# full_adder.net
KiCad netlist of a schematic drawn in EAGLE
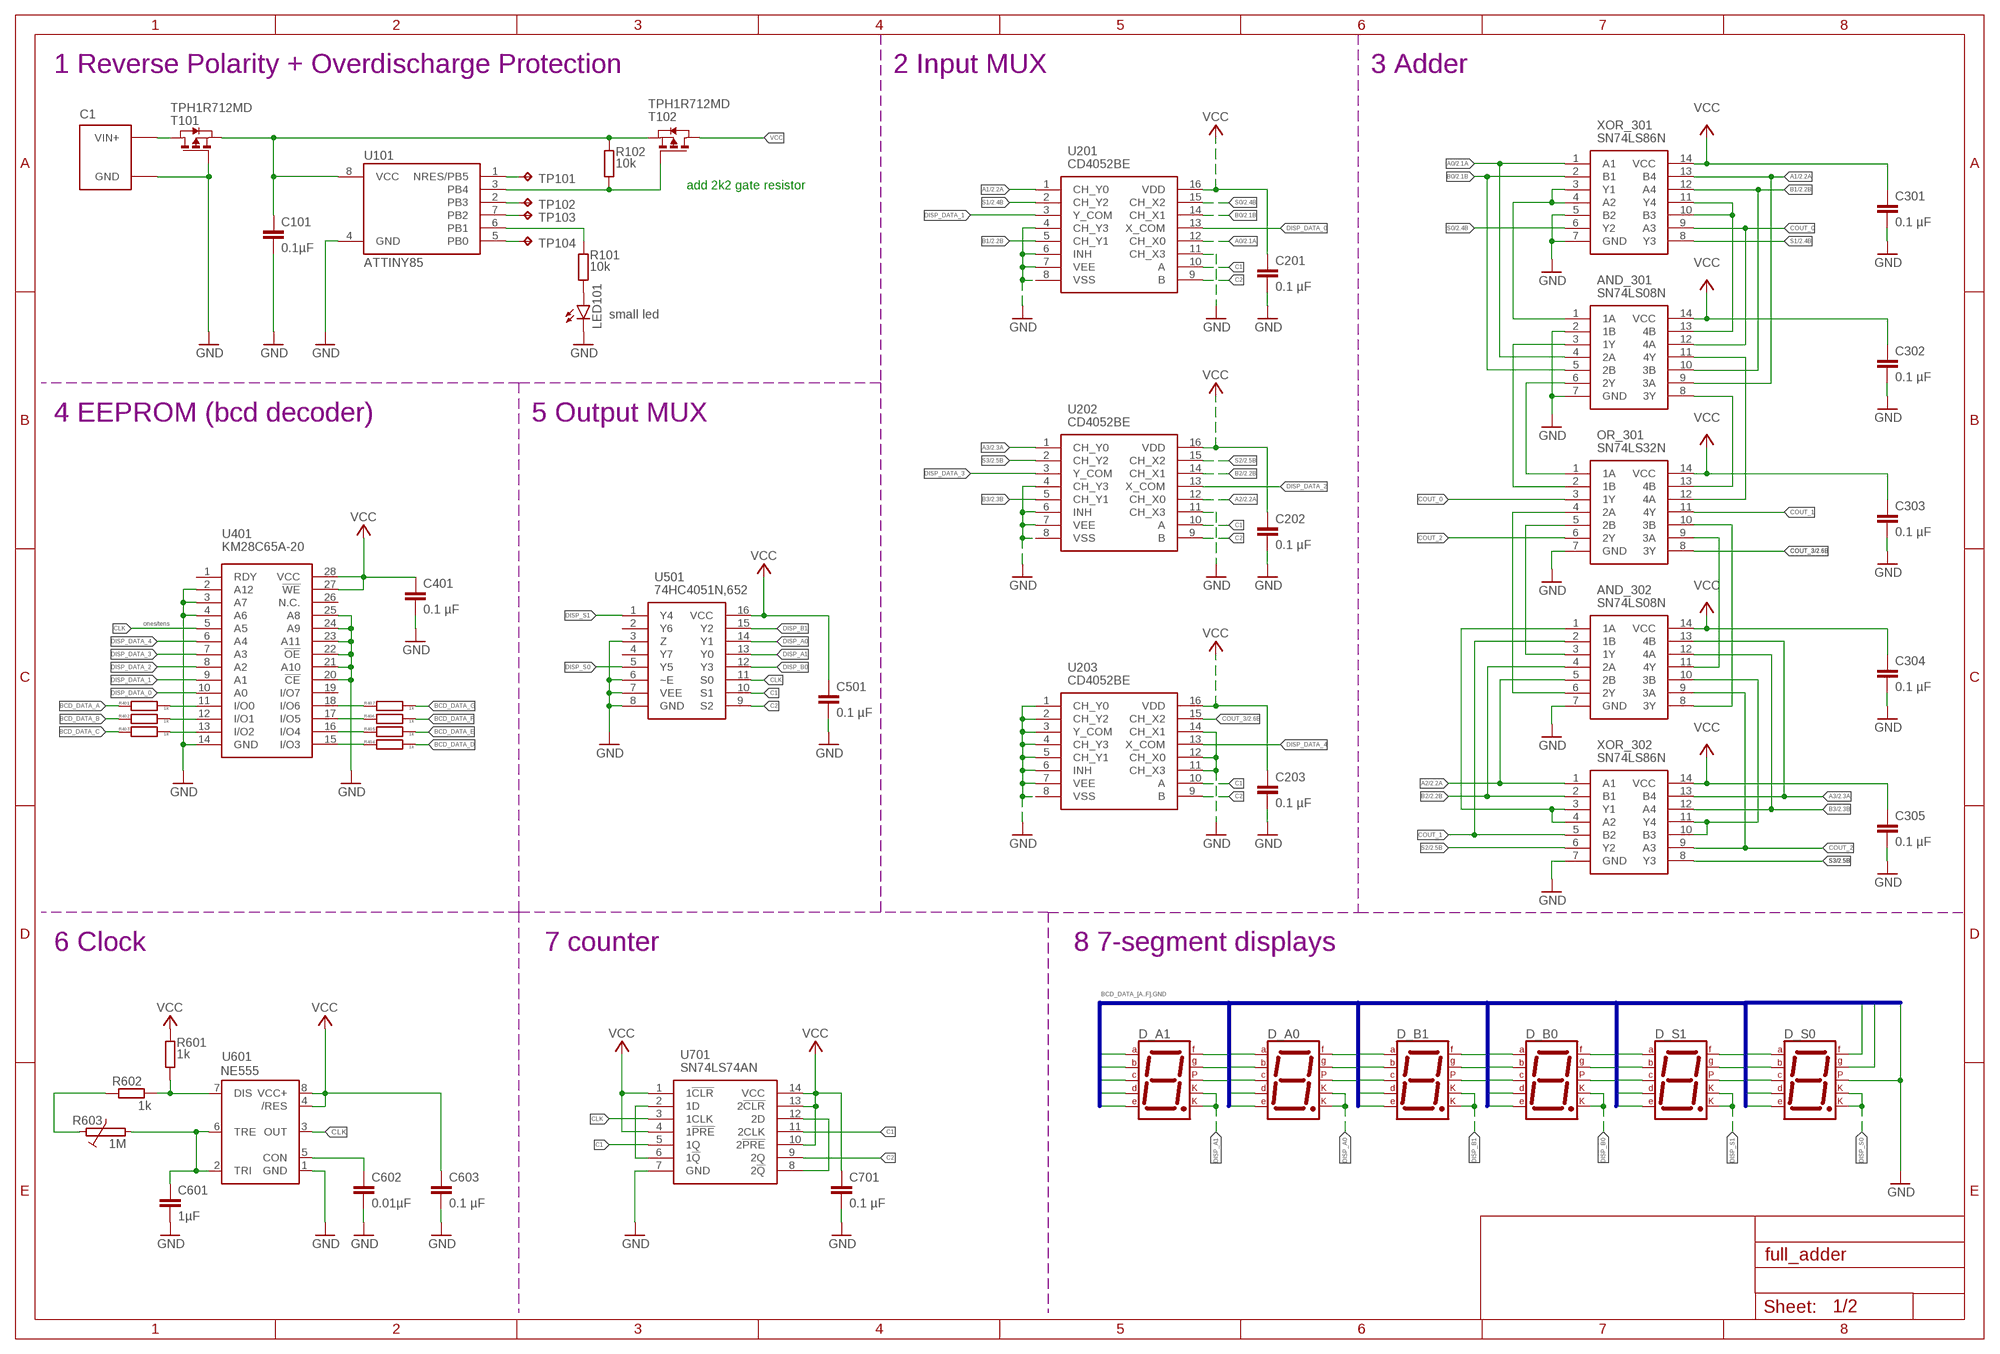
[diagram p0: schematic, sheet 1]
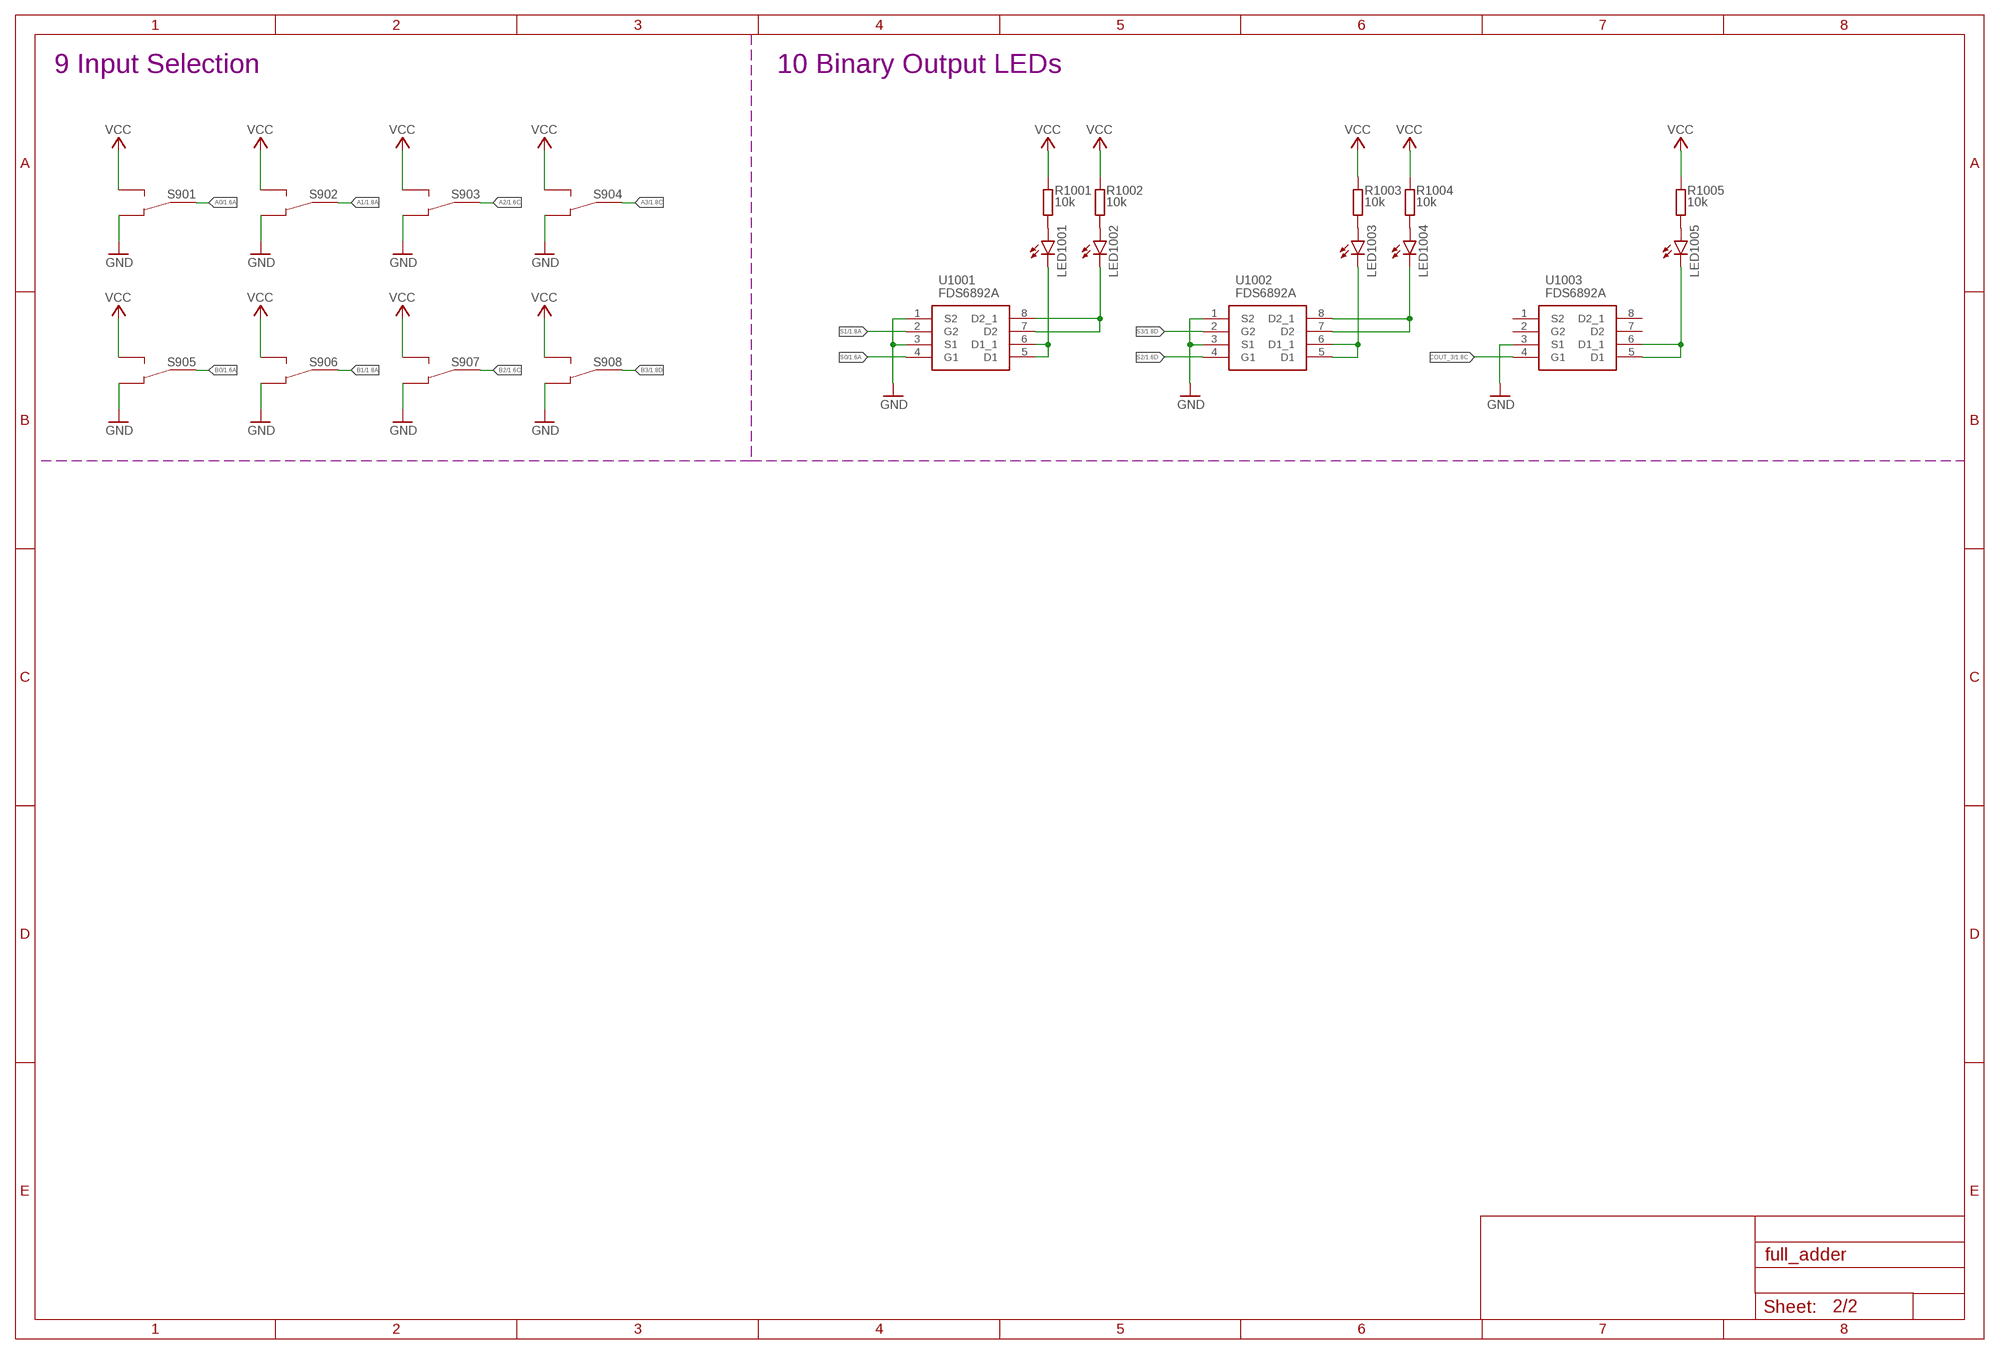
[diagram p1: schematic, sheet 2]

(export (version "E")
  (design (tool "Eeschema 10.0.6"))
  (components
    (comp (ref "AND_301")
      (value "SN74LS08N")
      (footprint "eagle-import:DIP794W53P254L1930H508Q14N")
      (fields (field (name "MOUSER_PART_NUMBER") "595-SN74LS08N") (field (name "RS_PART_NUMBER") "0307519P"))
      (libsource (lib "eagle-import") (part "SN74LS08N"))
    )
    (comp (ref "AND_302")
      (value "SN74LS08N")
      (footprint "eagle-import:DIP794W53P254L1930H508Q14N")
      (fields (field (name "MOUSER_PART_NUMBER") "595-SN74LS08N") (field (name "RS_PART_NUMBER") "0307519P"))
      (libsource (lib "eagle-import") (part "SN74LS08N"))
    )
    (comp (ref "C1")
      (value "BATTERY_CONNECTOR")
      (footprint "eagle-import:BATTERY_CONNECTOR")
      (libsource (lib "eagle-import") (part "BATTERY_CONNECTOR"))
    )
    (comp (ref "C101")
      (value "0.1µF")
      (footprint "eagle-import:C1206")
      (libsource (lib "eagle-import") (part "C-EUC1206"))
    )
    (comp (ref "C201")
      (value "0.1 µF")
      (footprint "eagle-import:C1206")
      (libsource (lib "eagle-import") (part "C-EUC1206"))
    )
    (comp (ref "C202")
      (value "0.1 µF")
      (footprint "eagle-import:C1206")
      (libsource (lib "eagle-import") (part "C-EUC1206"))
    )
    (comp (ref "C203")
      (value "0.1 µF")
      (footprint "eagle-import:C1206")
      (libsource (lib "eagle-import") (part "C-EUC1206"))
    )
    (comp (ref "C301")
      (value "0.1 µF")
      (footprint "eagle-import:C1206")
      (libsource (lib "eagle-import") (part "C-EUC1206"))
    )
    (comp (ref "C302")
      (value "0.1 µF")
      (footprint "eagle-import:C1206")
      (libsource (lib "eagle-import") (part "C-EUC1206"))
    )
    (comp (ref "C303")
      (value "0.1 µF")
      (footprint "eagle-import:C1206")
      (libsource (lib "eagle-import") (part "C-EUC1206"))
    )
    (comp (ref "C304")
      (value "0.1 µF")
      (footprint "eagle-import:C1206")
      (libsource (lib "eagle-import") (part "C-EUC1206"))
    )
    (comp (ref "C305")
      (value "0.1 µF")
      (footprint "eagle-import:C1206")
      (libsource (lib "eagle-import") (part "C-EUC1206"))
    )
    (comp (ref "C401")
      (value "0.1 µF")
      (footprint "eagle-import:C1206")
      (libsource (lib "eagle-import") (part "C-EUC1206"))
    )
    (comp (ref "C501")
      (value "0.1 µF")
      (footprint "eagle-import:C1206")
      (libsource (lib "eagle-import") (part "C-EUC1206"))
    )
    (comp (ref "C601")
      (value "1µF")
      (footprint "eagle-import:C050-024X044")
      (libsource (lib "eagle-import") (part "C-EU050-024X044"))
    )
    (comp (ref "C602")
      (value "0.01µF")
      (footprint "eagle-import:C050-024X044")
      (libsource (lib "eagle-import") (part "C-EU050-024X044"))
    )
    (comp (ref "C603")
      (value "0.1 µF")
      (footprint "eagle-import:C1206")
      (libsource (lib "eagle-import") (part "C-EUC1206"))
    )
    (comp (ref "C701")
      (value "0.1 µF")
      (footprint "eagle-import:C1206")
      (libsource (lib "eagle-import") (part "C-EUC1206"))
    )
    (comp (ref "D_A0")
      (value "7SEG-CK")
      (footprint "eagle-import:7SEG-13")
      (libsource (lib "eagle-import") (part "7SEG-CK"))
    )
    (comp (ref "D_A1")
      (value "7SEG-CK")
      (footprint "eagle-import:7SEG-13")
      (libsource (lib "eagle-import") (part "7SEG-CK"))
    )
    (comp (ref "D_B0")
      (value "7SEG-CK")
      (footprint "eagle-import:7SEG-13")
      (libsource (lib "eagle-import") (part "7SEG-CK"))
    )
    (comp (ref "D_B1")
      (value "7SEG-CK")
      (footprint "eagle-import:7SEG-13")
      (libsource (lib "eagle-import") (part "7SEG-CK"))
    )
    (comp (ref "D_S0")
      (value "7SEG-CK")
      (footprint "eagle-import:7SEG-13")
      (libsource (lib "eagle-import") (part "7SEG-CK"))
    )
    (comp (ref "D_S1")
      (value "7SEG-CK")
      (footprint "eagle-import:7SEG-13")
      (libsource (lib "eagle-import") (part "7SEG-CK"))
    )
    (comp (ref "LED101")
      (value "LED3MM")
      (footprint "eagle-import:LED3MM")
      (libsource (lib "eagle-import") (part "LED3MM"))
    )
    (comp (ref "OR_301")
      (value "SN74LS32N")
      (footprint "eagle-import:DIP794W53P254L1930H508Q14N")
      (fields (field (name "MOUSER_PART_NUMBER") "595-SN74LS32N") (field (name "RS_PART_NUMBER") "0307569P"))
      (libsource (lib "eagle-import") (part "SN74LS32N"))
    )
    (comp (ref "R101")
      (value "10k")
      (footprint "eagle-import:R1206")
      (libsource (lib "eagle-import") (part "R-EU_R1206"))
    )
    (comp (ref "R102")
      (value "10k")
      (footprint "eagle-import:R1206")
      (libsource (lib "eagle-import") (part "R-EU_R1206"))
    )
    (comp (ref "R401")
      (value "1k")
      (footprint "eagle-import:R1206")
      (libsource (lib "eagle-import") (part "R-EU_R1206"))
    )
    (comp (ref "R402")
      (value "1k")
      (footprint "eagle-import:R1206")
      (libsource (lib "eagle-import") (part "R-EU_R1206"))
    )
    (comp (ref "R403")
      (value "1k")
      (footprint "eagle-import:R1206")
      (libsource (lib "eagle-import") (part "R-EU_R1206"))
    )
    (comp (ref "R404")
      (value "1k")
      (footprint "eagle-import:R1206")
      (libsource (lib "eagle-import") (part "R-EU_R1206"))
    )
    (comp (ref "R405")
      (value "1k")
      (footprint "eagle-import:R1206")
      (libsource (lib "eagle-import") (part "R-EU_R1206"))
    )
    (comp (ref "R406")
      (value "1k")
      (footprint "eagle-import:R1206")
      (libsource (lib "eagle-import") (part "R-EU_R1206"))
    )
    (comp (ref "R407")
      (value "1k")
      (footprint "eagle-import:R1206")
      (libsource (lib "eagle-import") (part "R-EU_R1206"))
    )
    (comp (ref "R601")
      (value "1k")
      (footprint "eagle-import:R1206")
      (libsource (lib "eagle-import") (part "R-EU_R1206"))
    )
    (comp (ref "R602")
      (value "1k")
      (footprint "eagle-import:R1206")
      (libsource (lib "eagle-import") (part "R-EU_R1206"))
    )
    (comp (ref "R603")
      (value "1M")
      (footprint "eagle-import:POTENTIOMETER")
      (libsource (lib "eagle-import") (part "POTENTIOMETER"))
    )
    (comp (ref "T101")
      (value "TPH1R712MD")
      (footprint "eagle-import:TPH1R712MDL1Q")
      (libsource (lib "eagle-import") (part "TPH1R712MD"))
    )
    (comp (ref "T102")
      (value "TPH1R712MD")
      (footprint "eagle-import:TPH1R712MDL1Q")
      (libsource (lib "eagle-import") (part "TPH1R712MD"))
    )
    (comp (ref "TP101")
      (value "TPB2,54")
      (footprint "eagle-import:B2,54")
      (libsource (lib "eagle-import") (part "TPB2,54"))
    )
    (comp (ref "TP102")
      (value "TPB2,54")
      (footprint "eagle-import:B2,54")
      (libsource (lib "eagle-import") (part "TPB2,54"))
    )
    (comp (ref "TP103")
      (value "TPB2,54")
      (footprint "eagle-import:B2,54")
      (libsource (lib "eagle-import") (part "TPB2,54"))
    )
    (comp (ref "TP104")
      (value "TPB2,54")
      (footprint "eagle-import:B2,54")
      (libsource (lib "eagle-import") (part "TPB2,54"))
    )
    (comp (ref "U101")
      (value "ATTINY85")
      (footprint "eagle-import:PDIP08_300MIL")
      (libsource (lib "eagle-import") (part "ATTINY45P-20"))
    )
    (comp (ref "U201")
      (value "CD4052BE")
      (footprint "eagle-import:DIP794W53P254L1930H508Q16N")
      (fields (field (name "MOUSER_PART_NUMBER") "595-CD4052BE") (field (name "RS_PART_NUMBER") "5036105"))
      (libsource (lib "eagle-import") (part "CD4052BE"))
    )
    (comp (ref "U202")
      (value "CD4052BE")
      (footprint "eagle-import:DIP794W53P254L1930H508Q16N")
      (fields (field (name "MOUSER_PART_NUMBER") "595-CD4052BE") (field (name "RS_PART_NUMBER") "5036105"))
      (libsource (lib "eagle-import") (part "CD4052BE"))
    )
    (comp (ref "U203")
      (value "CD4052BE")
      (footprint "eagle-import:DIP794W53P254L1930H508Q16N")
      (fields (field (name "MOUSER_PART_NUMBER") "595-CD4052BE") (field (name "RS_PART_NUMBER") "5036105"))
      (libsource (lib "eagle-import") (part "CD4052BE"))
    )
    (comp (ref "U401")
      (value "KM28C65A-20")
      (footprint "eagle-import:KM28C65A-20")
      (libsource (lib "eagle-import") (part "KM28C65A-20"))
    )
    (comp (ref "U501")
      (value "74HC4051N,652")
      (footprint "eagle-import:DIP254P762X420-16")
      (libsource (lib "eagle-import") (part "74HC4051N,652"))
    )
    (comp (ref "U601")
      (value "NE555")
      (footprint "eagle-import:DIL-08")
      (fields (field (name "MF") "Arrow Electronics") (field (name "MPN") "NE555N"))
      (libsource (lib "eagle-import") (part "NE555"))
    )
    (comp (ref "U701")
      (value "SN74LS74AN")
      (footprint "eagle-import:DIP794W53P254L1930H508Q14N")
      (fields (field (name "MOUSER_PART_NUMBER") "595-SN74LS74AN") (field (name "RS_PART_NUMBER") "0307597P"))
      (libsource (lib "eagle-import") (part "SN74LS74AN"))
    )
    (comp (ref "XOR_301")
      (value "SN74LS86N")
      (footprint "eagle-import:DIP762W53P254L1848H469Q14N")
      (fields (field (name "RS_PART_NUMBER") "0644234"))
      (libsource (lib "eagle-import") (part "SN74LS86N"))
    )
    (comp (ref "XOR_302")
      (value "SN74LS86N")
      (footprint "eagle-import:DIP762W53P254L1848H469Q14N")
      (fields (field (name "RS_PART_NUMBER") "0644234"))
      (libsource (lib "eagle-import") (part "SN74LS86N"))
    )
    (comp (ref "LED1001")
      (value "LED3MM")
      (footprint "eagle-import:LED3MM")
      (libsource (lib "eagle-import") (part "LED3MM"))
    )
    (comp (ref "LED1002")
      (value "LED3MM")
      (footprint "eagle-import:LED3MM")
      (libsource (lib "eagle-import") (part "LED3MM"))
    )
    (comp (ref "LED1003")
      (value "LED3MM")
      (footprint "eagle-import:LED3MM")
      (libsource (lib "eagle-import") (part "LED3MM"))
    )
    (comp (ref "LED1004")
      (value "LED3MM")
      (footprint "eagle-import:LED3MM")
      (libsource (lib "eagle-import") (part "LED3MM"))
    )
    (comp (ref "LED1005")
      (value "LED3MM")
      (footprint "eagle-import:LED3MM")
      (libsource (lib "eagle-import") (part "LED3MM"))
    )
    (comp (ref "R1001")
      (value "10k")
      (footprint "eagle-import:R1206")
      (libsource (lib "eagle-import") (part "R-EU_R1206"))
    )
    (comp (ref "R1002")
      (value "10k")
      (footprint "eagle-import:R1206")
      (libsource (lib "eagle-import") (part "R-EU_R1206"))
    )
    (comp (ref "R1003")
      (value "10k")
      (footprint "eagle-import:R1206")
      (libsource (lib "eagle-import") (part "R-EU_R1206"))
    )
    (comp (ref "R1004")
      (value "10k")
      (footprint "eagle-import:R1206")
      (libsource (lib "eagle-import") (part "R-EU_R1206"))
    )
    (comp (ref "R1005")
      (value "10k")
      (footprint "eagle-import:R1206")
      (libsource (lib "eagle-import") (part "R-EU_R1206"))
    )
    (comp (ref "S901")
      (value "TOGGLESWITCH")
      (footprint "eagle-import:TOGGLESWITCH")
      (libsource (lib "eagle-import") (part "TOGGLESWITCH"))
    )
    (comp (ref "S902")
      (value "TOGGLESWITCH")
      (footprint "eagle-import:TOGGLESWITCH")
      (libsource (lib "eagle-import") (part "TOGGLESWITCH"))
    )
    (comp (ref "S903")
      (value "TOGGLESWITCH")
      (footprint "eagle-import:TOGGLESWITCH")
      (libsource (lib "eagle-import") (part "TOGGLESWITCH"))
    )
    (comp (ref "S904")
      (value "TOGGLESWITCH")
      (footprint "eagle-import:TOGGLESWITCH")
      (libsource (lib "eagle-import") (part "TOGGLESWITCH"))
    )
    (comp (ref "S905")
      (value "TOGGLESWITCH")
      (footprint "eagle-import:TOGGLESWITCH")
      (libsource (lib "eagle-import") (part "TOGGLESWITCH"))
    )
    (comp (ref "S906")
      (value "TOGGLESWITCH")
      (footprint "eagle-import:TOGGLESWITCH")
      (libsource (lib "eagle-import") (part "TOGGLESWITCH"))
    )
    (comp (ref "S907")
      (value "TOGGLESWITCH")
      (footprint "eagle-import:TOGGLESWITCH")
      (libsource (lib "eagle-import") (part "TOGGLESWITCH"))
    )
    (comp (ref "S908")
      (value "TOGGLESWITCH")
      (footprint "eagle-import:TOGGLESWITCH")
      (libsource (lib "eagle-import") (part "TOGGLESWITCH"))
    )
    (comp (ref "U1001")
      (value "FDS6892A")
      (footprint "eagle-import:SOIC127P600X175-8N")
      (fields (field (name "MOUSER_PART_NUMBER") "512-FDS6892A"))
      (libsource (lib "eagle-import") (part "FDS6892A"))
    )
    (comp (ref "U1002")
      (value "FDS6892A")
      (footprint "eagle-import:SOIC127P600X175-8N")
      (fields (field (name "MOUSER_PART_NUMBER") "512-FDS6892A"))
      (libsource (lib "eagle-import") (part "FDS6892A"))
    )
    (comp (ref "U1003")
      (value "FDS6892A")
      (footprint "eagle-import:SOIC127P600X175-8N")
      (fields (field (name "MOUSER_PART_NUMBER") "512-FDS6892A"))
      (libsource (lib "eagle-import") (part "FDS6892A"))
    )
  )
  (nets
    (net (code "1") (name "A0") (class "Default")
      (node (ref "AND_301") (pin "4") (pinfunction "2A_4") (pintype "bidirectional"))
      (node (ref "S901") (pin "OUT") (pinfunction "P$X_OUT") (pintype "bidirectional"))
      (node (ref "U201") (pin "12") (pinfunction "CH_X0_12") (pintype "bidirectional"))
      (node (ref "XOR_301") (pin "1") (pinfunction "A1_1") (pintype "bidirectional"))
    )
    (net (code "2") (name "A1") (class "Default")
      (node (ref "AND_301") (pin "9") (pinfunction "3A_9") (pintype "bidirectional"))
      (node (ref "S902") (pin "OUT") (pinfunction "P$X_OUT") (pintype "bidirectional"))
      (node (ref "U201") (pin "1") (pinfunction "CH_Y0_1") (pintype "bidirectional"))
      (node (ref "XOR_301") (pin "13") (pinfunction "B4_13") (pintype "bidirectional"))
    )
    (net (code "3") (name "A2") (class "Default")
      (node (ref "AND_302") (pin "5") (pinfunction "2B_5") (pintype "bidirectional"))
      (node (ref "S903") (pin "OUT") (pinfunction "P$X_OUT") (pintype "bidirectional"))
      (node (ref "U202") (pin "12") (pinfunction "CH_X0_12") (pintype "bidirectional"))
      (node (ref "XOR_302") (pin "1") (pinfunction "A1_1") (pintype "bidirectional"))
    )
    (net (code "4") (name "A3") (class "Default")
      (node (ref "AND_302") (pin "13") (pinfunction "4B_13") (pintype "bidirectional"))
      (node (ref "S904") (pin "OUT") (pinfunction "P$X_OUT") (pintype "bidirectional"))
      (node (ref "U202") (pin "1") (pinfunction "CH_Y0_1") (pintype "bidirectional"))
      (node (ref "XOR_302") (pin "13") (pinfunction "B4_13") (pintype "bidirectional"))
    )
    (net (code "5") (name "B0") (class "Default")
      (node (ref "AND_301") (pin "5") (pinfunction "2B_5") (pintype "bidirectional"))
      (node (ref "S905") (pin "OUT") (pinfunction "P$X_OUT") (pintype "bidirectional"))
      (node (ref "U201") (pin "14") (pinfunction "CH_X1_14") (pintype "bidirectional"))
      (node (ref "XOR_301") (pin "2") (pinfunction "B1_2") (pintype "bidirectional"))
    )
    (net (code "6") (name "B1") (class "Default")
      (node (ref "AND_301") (pin "10") (pinfunction "3B_10") (pintype "bidirectional"))
      (node (ref "S906") (pin "OUT") (pinfunction "P$X_OUT") (pintype "bidirectional"))
      (node (ref "U201") (pin "5") (pinfunction "CH_Y1_5") (pintype "bidirectional"))
      (node (ref "XOR_301") (pin "12") (pinfunction "A4_12") (pintype "bidirectional"))
    )
    (net (code "7") (name "B2") (class "Default")
      (node (ref "AND_302") (pin "4") (pinfunction "2A_4") (pintype "bidirectional"))
      (node (ref "S907") (pin "OUT") (pinfunction "P$X_OUT") (pintype "bidirectional"))
      (node (ref "U202") (pin "14") (pinfunction "CH_X1_14") (pintype "bidirectional"))
      (node (ref "XOR_302") (pin "2") (pinfunction "B1_2") (pintype "bidirectional"))
    )
    (net (code "8") (name "B3") (class "Default")
      (node (ref "AND_302") (pin "12") (pinfunction "4A_12") (pintype "bidirectional"))
      (node (ref "S908") (pin "OUT") (pinfunction "P$X_OUT") (pintype "bidirectional"))
      (node (ref "U202") (pin "5") (pinfunction "CH_Y1_5") (pintype "bidirectional"))
      (node (ref "XOR_302") (pin "12") (pinfunction "A4_12") (pintype "bidirectional"))
    )
    (net (code "9") (name "BCD_DATA_A") (class "Default")
      (node (ref "D_A0") (pin "7") (pinfunction "A_7") (pintype "passive"))
      (node (ref "D_A1") (pin "7") (pinfunction "A_7") (pintype "passive"))
      (node (ref "D_B0") (pin "7") (pinfunction "A_7") (pintype "passive"))
      (node (ref "D_B1") (pin "7") (pinfunction "A_7") (pintype "passive"))
      (node (ref "D_S0") (pin "7") (pinfunction "A_7") (pintype "passive"))
      (node (ref "D_S1") (pin "7") (pinfunction "A_7") (pintype "passive"))
      (node (ref "R401") (pin "1") (pinfunction "1_1") (pintype "passive"))
    )
    (net (code "10") (name "BCD_DATA_B") (class "Default")
      (node (ref "D_A0") (pin "6") (pinfunction "B_6") (pintype "passive"))
      (node (ref "D_A1") (pin "6") (pinfunction "B_6") (pintype "passive"))
      (node (ref "D_B0") (pin "6") (pinfunction "B_6") (pintype "passive"))
      (node (ref "D_B1") (pin "6") (pinfunction "B_6") (pintype "passive"))
      (node (ref "D_S0") (pin "6") (pinfunction "B_6") (pintype "passive"))
      (node (ref "D_S1") (pin "6") (pinfunction "B_6") (pintype "passive"))
      (node (ref "R402") (pin "1") (pinfunction "1_1") (pintype "passive"))
    )
    (net (code "11") (name "BCD_DATA_C") (class "Default")
      (node (ref "D_A0") (pin "4") (pinfunction "C_4") (pintype "passive"))
      (node (ref "D_A1") (pin "4") (pinfunction "C_4") (pintype "passive"))
      (node (ref "D_B0") (pin "4") (pinfunction "C_4") (pintype "passive"))
      (node (ref "D_B1") (pin "4") (pinfunction "C_4") (pintype "passive"))
      (node (ref "D_S0") (pin "4") (pinfunction "C_4") (pintype "passive"))
      (node (ref "D_S1") (pin "4") (pinfunction "C_4") (pintype "passive"))
      (node (ref "R403") (pin "1") (pinfunction "1_1") (pintype "passive"))
    )
    (net (code "12") (name "BCD_DATA_D") (class "Default")
      (node (ref "D_A0") (pin "2") (pinfunction "D_2") (pintype "passive"))
      (node (ref "D_A1") (pin "2") (pinfunction "D_2") (pintype "passive"))
      (node (ref "D_B0") (pin "2") (pinfunction "D_2") (pintype "passive"))
      (node (ref "D_B1") (pin "2") (pinfunction "D_2") (pintype "passive"))
      (node (ref "D_S0") (pin "2") (pinfunction "D_2") (pintype "passive"))
      (node (ref "D_S1") (pin "2") (pinfunction "D_2") (pintype "passive"))
      (node (ref "R404") (pin "2") (pinfunction "2_2") (pintype "passive"))
    )
    (net (code "13") (name "BCD_DATA_E") (class "Default")
      (node (ref "D_A0") (pin "1") (pinfunction "E_1") (pintype "passive"))
      (node (ref "D_A1") (pin "1") (pinfunction "E_1") (pintype "passive"))
      (node (ref "D_B0") (pin "1") (pinfunction "E_1") (pintype "passive"))
      (node (ref "D_B1") (pin "1") (pinfunction "E_1") (pintype "passive"))
      (node (ref "D_S0") (pin "1") (pinfunction "E_1") (pintype "passive"))
      (node (ref "D_S1") (pin "1") (pinfunction "E_1") (pintype "passive"))
      (node (ref "R405") (pin "2") (pinfunction "2_2") (pintype "passive"))
    )
    (net (code "14") (name "BCD_DATA_F") (class "Default")
      (node (ref "D_A0") (pin "9") (pinfunction "F_9") (pintype "passive"))
      (node (ref "D_A1") (pin "9") (pinfunction "F_9") (pintype "passive"))
      (node (ref "D_B0") (pin "9") (pinfunction "F_9") (pintype "passive"))
      (node (ref "D_B1") (pin "9") (pinfunction "F_9") (pintype "passive"))
      (node (ref "D_S0") (pin "9") (pinfunction "F_9") (pintype "passive"))
      (node (ref "D_S1") (pin "9") (pinfunction "F_9") (pintype "passive"))
      (node (ref "R406") (pin "2") (pinfunction "2_2") (pintype "passive"))
    )
    (net (code "15") (name "BCD_DATA_G") (class "Default")
      (node (ref "D_A0") (pin "10") (pinfunction "G_10") (pintype "passive"))
      (node (ref "D_A1") (pin "10") (pinfunction "G_10") (pintype "passive"))
      (node (ref "D_B0") (pin "10") (pinfunction "G_10") (pintype "passive"))
      (node (ref "D_B1") (pin "10") (pinfunction "G_10") (pintype "passive"))
      (node (ref "D_S0") (pin "10") (pinfunction "G_10") (pintype "passive"))
      (node (ref "D_S1") (pin "10") (pinfunction "G_10") (pintype "passive"))
      (node (ref "R407") (pin "2") (pinfunction "2_2") (pintype "passive"))
    )
    (net (code "16") (name "C1") (class "Default")
      (node (ref "U201") (pin "10") (pinfunction "A_10") (pintype "bidirectional"))
      (node (ref "U202") (pin "10") (pinfunction "A_10") (pintype "bidirectional"))
      (node (ref "U203") (pin "10") (pinfunction "A_10") (pintype "bidirectional"))
      (node (ref "U501") (pin "10") (pinfunction "S1_10") (pintype "bidirectional"))
      (node (ref "U701") (pin "11") (pinfunction "2CLK_11") (pintype "bidirectional"))
      (node (ref "U701") (pin "5") (pinfunction "1Q_5") (pintype "bidirectional"))
    )
    (net (code "17") (name "C2") (class "Default")
      (node (ref "U201") (pin "9") (pinfunction "B_9") (pintype "bidirectional"))
      (node (ref "U202") (pin "9") (pinfunction "B_9") (pintype "bidirectional"))
      (node (ref "U203") (pin "9") (pinfunction "B_9") (pintype "bidirectional"))
      (node (ref "U501") (pin "9") (pinfunction "S2_9") (pintype "bidirectional"))
      (node (ref "U701") (pin "9") (pinfunction "2Q_9") (pintype "bidirectional"))
    )
    (net (code "18") (name "CLK") (class "Default")
      (node (ref "U401") (pin "5") (pinfunction "A5_5") (pintype "bidirectional"))
      (node (ref "U501") (pin "11") (pinfunction "S0_11") (pintype "bidirectional"))
      (node (ref "U601") (pin "3") (pinfunction "OUT_3") (pintype "output"))
      (node (ref "U701") (pin "3") (pinfunction "1CLK_3") (pintype "bidirectional"))
    )
    (net (code "19") (name "COUT_0") (class "Default")
      (node (ref "AND_301") (pin "12") (pinfunction "4A_12") (pintype "bidirectional"))
      (node (ref "OR_301") (pin "3") (pinfunction "1Y_3") (pintype "bidirectional"))
      (node (ref "XOR_301") (pin "9") (pinfunction "A3_9") (pintype "bidirectional"))
    )
    (net (code "20") (name "COUT_1") (class "Default")
      (node (ref "AND_302") (pin "2") (pinfunction "1B_2") (pintype "bidirectional"))
      (node (ref "OR_301") (pin "11") (pinfunction "4Y_11") (pintype "bidirectional"))
      (node (ref "XOR_302") (pin "5") (pinfunction "B2_5") (pintype "bidirectional"))
    )
    (net (code "21") (name "COUT_2") (class "Default")
      (node (ref "AND_302") (pin "9") (pinfunction "3A_9") (pintype "bidirectional"))
      (node (ref "OR_301") (pin "6") (pinfunction "2Y_6") (pintype "bidirectional"))
      (node (ref "XOR_302") (pin "9") (pinfunction "A3_9") (pintype "bidirectional"))
    )
    (net (code "22") (name "COUT_3") (class "Default")
      (node (ref "OR_301") (pin "8") (pinfunction "3Y_8") (pintype "bidirectional"))
      (node (ref "U1003") (pin "4") (pinfunction "G1_4") (pintype "bidirectional"))
      (node (ref "U203") (pin "15") (pinfunction "CH_X2_15") (pintype "bidirectional"))
    )
    (net (code "23") (name "DISP_A0") (class "Default")
      (node (ref "D_A0") (pin "3") (pinfunction "CK1_3") (pintype "passive"))
      (node (ref "D_A0") (pin "8") (pinfunction "CK2_8") (pintype "passive"))
      (node (ref "U501") (pin "14") (pinfunction "Y1_14") (pintype "bidirectional"))
    )
    (net (code "24") (name "DISP_A1") (class "Default")
      (node (ref "D_A1") (pin "3") (pinfunction "CK1_3") (pintype "passive"))
      (node (ref "D_A1") (pin "8") (pinfunction "CK2_8") (pintype "passive"))
      (node (ref "U501") (pin "13") (pinfunction "Y0_13") (pintype "bidirectional"))
    )
    (net (code "25") (name "DISP_B0") (class "Default")
      (node (ref "D_B0") (pin "3") (pinfunction "CK1_3") (pintype "passive"))
      (node (ref "D_B0") (pin "8") (pinfunction "CK2_8") (pintype "passive"))
      (node (ref "U501") (pin "12") (pinfunction "Y3_12") (pintype "bidirectional"))
    )
    (net (code "26") (name "DISP_B1") (class "Default")
      (node (ref "D_B1") (pin "3") (pinfunction "CK1_3") (pintype "passive"))
      (node (ref "D_B1") (pin "8") (pinfunction "CK2_8") (pintype "passive"))
      (node (ref "U501") (pin "15") (pinfunction "Y2_15") (pintype "bidirectional"))
    )
    (net (code "27") (name "DISP_DATA_0") (class "Default")
      (node (ref "U201") (pin "13") (pinfunction "X_COM_13") (pintype "bidirectional"))
      (node (ref "U401") (pin "10") (pinfunction "A0_10") (pintype "bidirectional"))
    )
    (net (code "28") (name "DISP_DATA_1") (class "Default")
      (node (ref "U201") (pin "3") (pinfunction "Y_COM_3") (pintype "bidirectional"))
      (node (ref "U401") (pin "9") (pinfunction "A1_9") (pintype "bidirectional"))
    )
    (net (code "29") (name "DISP_DATA_2") (class "Default")
      (node (ref "U202") (pin "13") (pinfunction "X_COM_13") (pintype "bidirectional"))
      (node (ref "U401") (pin "8") (pinfunction "A2_8") (pintype "bidirectional"))
    )
    (net (code "30") (name "DISP_DATA_3") (class "Default")
      (node (ref "U202") (pin "3") (pinfunction "Y_COM_3") (pintype "bidirectional"))
      (node (ref "U401") (pin "7") (pinfunction "A3_7") (pintype "bidirectional"))
    )
    (net (code "31") (name "DISP_DATA_4") (class "Default")
      (node (ref "U203") (pin "13") (pinfunction "X_COM_13") (pintype "bidirectional"))
      (node (ref "U401") (pin "6") (pinfunction "A4_6") (pintype "bidirectional"))
    )
    (net (code "32") (name "DISP_S0") (class "Default")
      (node (ref "D_S0") (pin "3") (pinfunction "CK1_3") (pintype "passive"))
      (node (ref "D_S0") (pin "8") (pinfunction "CK2_8") (pintype "passive"))
      (node (ref "U501") (pin "5") (pinfunction "Y5_5") (pintype "bidirectional"))
    )
    (net (code "33") (name "DISP_S1") (class "Default")
      (node (ref "D_S1") (pin "3") (pinfunction "CK1_3") (pintype "passive"))
      (node (ref "D_S1") (pin "8") (pinfunction "CK2_8") (pintype "passive"))
      (node (ref "U501") (pin "1") (pinfunction "Y4_1") (pintype "bidirectional"))
    )
    (net (code "34") (name "GND") (class "Default")
      (node (ref "AND_301") (pin "2") (pinfunction "1B_2") (pintype "bidirectional"))
      (node (ref "AND_301") (pin "7") (pinfunction "GND_7") (pintype "bidirectional"))
      (node (ref "AND_302") (pin "7") (pinfunction "GND_7") (pintype "bidirectional"))
      (node (ref "C1") (pin "GND") (pinfunction "GND_GND") (pintype "bidirectional"))
      (node (ref "C101") (pin "2") (pinfunction "2_2") (pintype "passive"))
      (node (ref "C201") (pin "2") (pinfunction "2_2") (pintype "passive"))
      (node (ref "C202") (pin "2") (pinfunction "2_2") (pintype "passive"))
      (node (ref "C203") (pin "2") (pinfunction "2_2") (pintype "passive"))
      (node (ref "C301") (pin "2") (pinfunction "2_2") (pintype "passive"))
      (node (ref "C302") (pin "2") (pinfunction "2_2") (pintype "passive"))
      (node (ref "C303") (pin "2") (pinfunction "2_2") (pintype "passive"))
      (node (ref "C304") (pin "2") (pinfunction "2_2") (pintype "passive"))
      (node (ref "C305") (pin "2") (pinfunction "2_2") (pintype "passive"))
      (node (ref "C401") (pin "2") (pinfunction "2_2") (pintype "passive"))
      (node (ref "C501") (pin "2") (pinfunction "2_2") (pintype "passive"))
      (node (ref "C601") (pin "2") (pinfunction "2_2") (pintype "passive"))
      (node (ref "C602") (pin "2") (pinfunction "2_2") (pintype "passive"))
      (node (ref "C603") (pin "2") (pinfunction "2_2") (pintype "passive"))
      (node (ref "C701") (pin "2") (pinfunction "2_2") (pintype "passive"))
      (node (ref "D_A0") (pin "5") (pinfunction "DP_5") (pintype "passive"))
      (node (ref "D_A1") (pin "5") (pinfunction "DP_5") (pintype "passive"))
      (node (ref "D_B0") (pin "5") (pinfunction "DP_5") (pintype "passive"))
      (node (ref "D_B1") (pin "5") (pinfunction "DP_5") (pintype "passive"))
      (node (ref "D_S0") (pin "5") (pinfunction "DP_5") (pintype "passive"))
      (node (ref "D_S1") (pin "5") (pinfunction "DP_5") (pintype "passive"))
      (node (ref "LED101") (pin "K") (pinfunction "C_K") (pintype "passive"))
      (node (ref "OR_301") (pin "7") (pinfunction "GND_7") (pintype "bidirectional"))
      (node (ref "S901") (pin "GND") (pinfunction "P$A_GND") (pintype "bidirectional"))
      (node (ref "S902") (pin "GND") (pinfunction "P$A_GND") (pintype "bidirectional"))
      (node (ref "S903") (pin "GND") (pinfunction "P$A_GND") (pintype "bidirectional"))
      (node (ref "S904") (pin "GND") (pinfunction "P$A_GND") (pintype "bidirectional"))
      (node (ref "S905") (pin "GND") (pinfunction "P$A_GND") (pintype "bidirectional"))
      (node (ref "S906") (pin "GND") (pinfunction "P$A_GND") (pintype "bidirectional"))
      (node (ref "S907") (pin "GND") (pinfunction "P$A_GND") (pintype "bidirectional"))
      (node (ref "S908") (pin "GND") (pinfunction "P$A_GND") (pintype "bidirectional"))
      (node (ref "T101") (pin "4") (pinfunction "G_4") (pintype "passive"))
      (node (ref "U1001") (pin "1") (pinfunction "S2_1") (pintype "bidirectional"))
      (node (ref "U1001") (pin "3") (pinfunction "S1_3") (pintype "bidirectional"))
      (node (ref "U1002") (pin "1") (pinfunction "S2_1") (pintype "bidirectional"))
      (node (ref "U1002") (pin "3") (pinfunction "S1_3") (pintype "bidirectional"))
      (node (ref "U1003") (pin "3") (pinfunction "S1_3") (pintype "bidirectional"))
      (node (ref "U101") (pin "4") (pinfunction "GND_4") (pintype "power_in"))
      (node (ref "U201") (pin "11") (pinfunction "CH_X3_11") (pintype "bidirectional"))
      (node (ref "U201") (pin "4") (pinfunction "CH_Y3_4") (pintype "bidirectional"))
      (node (ref "U201") (pin "6") (pinfunction "INH_6") (pintype "bidirectional"))
      (node (ref "U201") (pin "7") (pinfunction "VEE_7") (pintype "bidirectional"))
      (node (ref "U201") (pin "8") (pinfunction "VSS_8") (pintype "bidirectional"))
      (node (ref "U202") (pin "11") (pinfunction "CH_X3_11") (pintype "bidirectional"))
      (node (ref "U202") (pin "4") (pinfunction "CH_Y3_4") (pintype "bidirectional"))
      (node (ref "U202") (pin "6") (pinfunction "INH_6") (pintype "bidirectional"))
      (node (ref "U202") (pin "7") (pinfunction "VEE_7") (pintype "bidirectional"))
      (node (ref "U202") (pin "8") (pinfunction "VSS_8") (pintype "bidirectional"))
      (node (ref "U203") (pin "1") (pinfunction "CH_Y0_1") (pintype "bidirectional"))
      (node (ref "U203") (pin "11") (pinfunction "CH_X3_11") (pintype "bidirectional"))
      (node (ref "U203") (pin "12") (pinfunction "CH_X0_12") (pintype "bidirectional"))
      (node (ref "U203") (pin "14") (pinfunction "CH_X1_14") (pintype "bidirectional"))
      (node (ref "U203") (pin "2") (pinfunction "CH_Y2_2") (pintype "bidirectional"))
      (node (ref "U203") (pin "3") (pinfunction "Y_COM_3") (pintype "bidirectional"))
      (node (ref "U203") (pin "4") (pinfunction "CH_Y3_4") (pintype "bidirectional"))
      (node (ref "U203") (pin "5") (pinfunction "CH_Y1_5") (pintype "bidirectional"))
      (node (ref "U203") (pin "6") (pinfunction "INH_6") (pintype "bidirectional"))
      (node (ref "U203") (pin "7") (pinfunction "VEE_7") (pintype "bidirectional"))
      (node (ref "U203") (pin "8") (pinfunction "VSS_8") (pintype "bidirectional"))
      (node (ref "U401") (pin "14") (pinfunction "GND_14") (pintype "bidirectional"))
      (node (ref "U401") (pin "2") (pinfunction "A12_2") (pintype "bidirectional"))
      (node (ref "U401") (pin "20") (pinfunction "~{CE}_20") (pintype "bidirectional"))
      (node (ref "U401") (pin "21") (pinfunction "A10_21") (pintype "bidirectional"))
      (node (ref "U401") (pin "22") (pinfunction "~{OE}_22") (pintype "bidirectional"))
      (node (ref "U401") (pin "23") (pinfunction "A11_23") (pintype "bidirectional"))
      (node (ref "U401") (pin "24") (pinfunction "A9_24") (pintype "bidirectional"))
      (node (ref "U401") (pin "25") (pinfunction "A8_25") (pintype "bidirectional"))
      (node (ref "U401") (pin "3") (pinfunction "A7_3") (pintype "bidirectional"))
      (node (ref "U401") (pin "4") (pinfunction "A6_4") (pintype "bidirectional"))
      (node (ref "U501") (pin "3") (pinfunction "Z_3") (pintype "bidirectional"))
      (node (ref "U501") (pin "6") (pinfunction "~{E}_6") (pintype "bidirectional"))
      (node (ref "U501") (pin "7") (pinfunction "VEE_7") (pintype "bidirectional"))
      (node (ref "U501") (pin "8") (pinfunction "GND_8") (pintype "bidirectional"))
      (node (ref "U601") (pin "1") (pinfunction "GND_1") (pintype "power_in"))
      (node (ref "U701") (pin "7") (pinfunction "GND_7") (pintype "bidirectional"))
      (node (ref "XOR_301") (pin "5") (pinfunction "B2_5") (pintype "bidirectional"))
      (node (ref "XOR_301") (pin "7") (pinfunction "GND_7") (pintype "bidirectional"))
      (node (ref "XOR_302") (pin "7") (pinfunction "GND_7") (pintype "bidirectional"))
    )
    (net (code "35") (name "Net-(AND_301-1A)") (class "Default")
      (node (ref "AND_301") (pin "1") (pinfunction "1A_1") (pintype "bidirectional"))
      (node (ref "XOR_301") (pin "3") (pinfunction "Y1_3") (pintype "bidirectional"))
      (node (ref "XOR_301") (pin "4") (pinfunction "A2_4") (pintype "bidirectional"))
    )
    (net (code "36") (name "Net-(AND_301-1Y)") (class "Default")
      (node (ref "AND_301") (pin "3") (pinfunction "1Y_3") (pintype "bidirectional"))
      (node (ref "OR_301") (pin "2") (pinfunction "1B_2") (pintype "bidirectional"))
    )
    (net (code "37") (name "Net-(AND_301-2Y)") (class "Default")
      (node (ref "AND_301") (pin "6") (pinfunction "2Y_6") (pintype "bidirectional"))
      (node (ref "OR_301") (pin "1") (pinfunction "1A_1") (pintype "bidirectional"))
    )
    (net (code "38") (name "Net-(AND_301-3Y)") (class "Default")
      (node (ref "AND_301") (pin "8") (pinfunction "3Y_8") (pintype "bidirectional"))
      (node (ref "OR_301") (pin "13") (pinfunction "4B_13") (pintype "bidirectional"))
    )
    (net (code "39") (name "Net-(AND_301-4B)") (class "Default")
      (node (ref "AND_301") (pin "13") (pinfunction "4B_13") (pintype "bidirectional"))
      (node (ref "XOR_301") (pin "10") (pinfunction "B3_10") (pintype "bidirectional"))
      (node (ref "XOR_301") (pin "11") (pinfunction "Y4_11") (pintype "bidirectional"))
    )
    (net (code "40") (name "Net-(AND_301-4Y)") (class "Default")
      (node (ref "AND_301") (pin "11") (pinfunction "4Y_11") (pintype "bidirectional"))
      (node (ref "OR_301") (pin "12") (pinfunction "4A_12") (pintype "bidirectional"))
    )
    (net (code "41") (name "Net-(AND_302-1A)") (class "Default")
      (node (ref "AND_302") (pin "1") (pinfunction "1A_1") (pintype "bidirectional"))
      (node (ref "XOR_302") (pin "3") (pinfunction "Y1_3") (pintype "bidirectional"))
      (node (ref "XOR_302") (pin "4") (pinfunction "A2_4") (pintype "bidirectional"))
    )
    (net (code "42") (name "Net-(AND_302-1Y)") (class "Default")
      (node (ref "AND_302") (pin "3") (pinfunction "1Y_3") (pintype "bidirectional"))
      (node (ref "OR_301") (pin "5") (pinfunction "2B_5") (pintype "bidirectional"))
    )
    (net (code "43") (name "Net-(AND_302-2Y)") (class "Default")
      (node (ref "AND_302") (pin "6") (pinfunction "2Y_6") (pintype "bidirectional"))
      (node (ref "OR_301") (pin "4") (pinfunction "2A_4") (pintype "bidirectional"))
    )
    (net (code "44") (name "Net-(AND_302-3B)") (class "Default")
      (node (ref "AND_302") (pin "10") (pinfunction "3B_10") (pintype "bidirectional"))
      (node (ref "XOR_302") (pin "10") (pinfunction "B3_10") (pintype "bidirectional"))
      (node (ref "XOR_302") (pin "11") (pinfunction "Y4_11") (pintype "bidirectional"))
    )
    (net (code "45") (name "Net-(AND_302-3Y)") (class "Default")
      (node (ref "AND_302") (pin "8") (pinfunction "3Y_8") (pintype "bidirectional"))
      (node (ref "OR_301") (pin "10") (pinfunction "3B_10") (pintype "bidirectional"))
    )
    (net (code "46") (name "Net-(AND_302-4Y)") (class "Default")
      (node (ref "AND_302") (pin "11") (pinfunction "4Y_11") (pintype "bidirectional"))
      (node (ref "OR_301") (pin "9") (pinfunction "3A_9") (pintype "bidirectional"))
    )
    (net (code "47") (name "Net-(C1-PadVIN+)") (class "Default")
      (node (ref "C1") (pin "VIN+") (pinfunction "VIN+_VIN+") (pintype "bidirectional"))
      (node (ref "T101") (pin "5") (pinfunction "D_5") (pintype "passive"))
      (node (ref "T101") (pin "6") (pinfunction "D_6") (pintype "passive"))
      (node (ref "T101") (pin "7") (pinfunction "D_7") (pintype "passive"))
      (node (ref "T101") (pin "8") (pinfunction "D_8") (pintype "passive"))
      (node (ref "T101") (pin "9") (pinfunction "D_9") (pintype "passive"))
    )
    (net (code "48") (name "Net-(LED101-PadA)") (class "Default")
      (node (ref "LED101") (pin "A") (pinfunction "A_A") (pintype "passive"))
      (node (ref "R101") (pin "1") (pinfunction "1_1") (pintype "passive"))
    )
    (net (code "49") (name "Net-(LED1001-C)") (class "Default")
      (node (ref "LED1001") (pin "K") (pinfunction "C_K") (pintype "passive"))
      (node (ref "U1001") (pin "5") (pinfunction "D1_5") (pintype "bidirectional"))
      (node (ref "U1001") (pin "6") (pinfunction "D1_1_6") (pintype "bidirectional"))
    )
    (net (code "50") (name "Net-(LED1001-PadA)") (class "Default")
      (node (ref "LED1001") (pin "A") (pinfunction "A_A") (pintype "passive"))
      (node (ref "R1001") (pin "1") (pinfunction "1_1") (pintype "passive"))
    )
    (net (code "51") (name "Net-(LED1002-C)") (class "Default")
      (node (ref "LED1002") (pin "K") (pinfunction "C_K") (pintype "passive"))
      (node (ref "U1001") (pin "7") (pinfunction "D2_7") (pintype "bidirectional"))
      (node (ref "U1001") (pin "8") (pinfunction "D2_1_8") (pintype "bidirectional"))
    )
    (net (code "52") (name "Net-(LED1002-PadA)") (class "Default")
      (node (ref "LED1002") (pin "A") (pinfunction "A_A") (pintype "passive"))
      (node (ref "R1002") (pin "1") (pinfunction "1_1") (pintype "passive"))
    )
    (net (code "53") (name "Net-(LED1003-C)") (class "Default")
      (node (ref "LED1003") (pin "K") (pinfunction "C_K") (pintype "passive"))
      (node (ref "U1002") (pin "5") (pinfunction "D1_5") (pintype "bidirectional"))
      (node (ref "U1002") (pin "6") (pinfunction "D1_1_6") (pintype "bidirectional"))
    )
    (net (code "54") (name "Net-(LED1003-PadA)") (class "Default")
      (node (ref "LED1003") (pin "A") (pinfunction "A_A") (pintype "passive"))
      (node (ref "R1003") (pin "1") (pinfunction "1_1") (pintype "passive"))
    )
    (net (code "55") (name "Net-(LED1004-C)") (class "Default")
      (node (ref "LED1004") (pin "K") (pinfunction "C_K") (pintype "passive"))
      (node (ref "U1002") (pin "7") (pinfunction "D2_7") (pintype "bidirectional"))
      (node (ref "U1002") (pin "8") (pinfunction "D2_1_8") (pintype "bidirectional"))
    )
    (net (code "56") (name "Net-(LED1004-PadA)") (class "Default")
      (node (ref "LED1004") (pin "A") (pinfunction "A_A") (pintype "passive"))
      (node (ref "R1004") (pin "1") (pinfunction "1_1") (pintype "passive"))
    )
    (net (code "57") (name "Net-(LED1005-C)") (class "Default")
      (node (ref "LED1005") (pin "K") (pinfunction "C_K") (pintype "passive"))
      (node (ref "U1003") (pin "5") (pinfunction "D1_5") (pintype "bidirectional"))
      (node (ref "U1003") (pin "6") (pinfunction "D1_1_6") (pintype "bidirectional"))
    )
    (net (code "58") (name "Net-(LED1005-PadA)") (class "Default")
      (node (ref "LED1005") (pin "A") (pinfunction "A_A") (pintype "passive"))
      (node (ref "R1005") (pin "1") (pinfunction "1_1") (pintype "passive"))
    )
    (net (code "59") (name "Net-(R603-P$1)") (class "Default")
      (node (ref "R602") (pin "1") (pinfunction "1_1") (pintype "passive"))
      (node (ref "R603") (pin "POT$1") (pinfunction "P$1_POT$1") (pintype "bidirectional"))
    )
    (net (code "60") (name "Net-(R603-P$2)") (class "Default")
      (node (ref "C601") (pin "1") (pinfunction "1_1") (pintype "passive"))
      (node (ref "R603") (pin "POT$2") (pinfunction "P$2_POT$2") (pintype "bidirectional"))
      (node (ref "U601") (pin "2") (pinfunction "TRI_2") (pintype "input"))
      (node (ref "U601") (pin "6") (pinfunction "TRE_6") (pintype "input"))
    )
    (net (code "61") (name "Net-(T102-G)") (class "Default")
      (node (ref "R102") (pin "1") (pinfunction "1_1") (pintype "passive"))
      (node (ref "T102") (pin "4") (pinfunction "G_4") (pintype "passive"))
      (node (ref "U101") (pin "3") (pinfunction "PB4_3") (pintype "bidirectional"))
    )
    (net (code "62") (name "Net-(U101-NRES{slash}PB5)") (class "Default")
      (node (ref "TP101") (pin "TP") (pinfunction "TP_TP") (pintype "input"))
      (node (ref "U101") (pin "1") (pinfunction "NRES/PB5_1") (pintype "bidirectional"))
    )
    (net (code "63") (name "Net-(U101-PB0)") (class "Default")
      (node (ref "TP104") (pin "TP") (pinfunction "TP_TP") (pintype "input"))
      (node (ref "U101") (pin "5") (pinfunction "PB0_5") (pintype "bidirectional"))
    )
    (net (code "64") (name "Net-(U101-PB1)") (class "Default")
      (node (ref "R101") (pin "2") (pinfunction "2_2") (pintype "passive"))
      (node (ref "U101") (pin "6") (pinfunction "PB1_6") (pintype "bidirectional"))
    )
    (net (code "65") (name "Net-(U101-PB2)") (class "Default")
      (node (ref "TP103") (pin "TP") (pinfunction "TP_TP") (pintype "input"))
      (node (ref "U101") (pin "7") (pinfunction "PB2_7") (pintype "bidirectional"))
    )
    (net (code "66") (name "Net-(U101-PB3)") (class "Default")
      (node (ref "TP102") (pin "TP") (pinfunction "TP_TP") (pintype "input"))
      (node (ref "U101") (pin "2") (pinfunction "PB3_2") (pintype "bidirectional"))
    )
    (net (code "67") (name "Net-(U101-VCC)") (class "Default")
      (node (ref "C101") (pin "1") (pinfunction "1_1") (pintype "passive"))
      (node (ref "R102") (pin "2") (pinfunction "2_2") (pintype "passive"))
      (node (ref "T101") (pin "1") (pinfunction "S_1") (pintype "passive"))
      (node (ref "T101") (pin "2") (pinfunction "S_2") (pintype "passive"))
      (node (ref "T101") (pin "3") (pinfunction "S_3") (pintype "passive"))
      (node (ref "T102") (pin "1") (pinfunction "S_1") (pintype "passive"))
      (node (ref "T102") (pin "2") (pinfunction "S_2") (pintype "passive"))
      (node (ref "T102") (pin "3") (pinfunction "S_3") (pintype "passive"))
      (node (ref "U101") (pin "8") (pinfunction "VCC_8") (pintype "power_in"))
    )
    (net (code "68") (name "Net-(U401-I{slash}O0)") (class "Default")
      (node (ref "R401") (pin "2") (pinfunction "2_2") (pintype "passive"))
      (node (ref "U401") (pin "11") (pinfunction "I/O0_11") (pintype "bidirectional"))
    )
    (net (code "69") (name "Net-(U401-I{slash}O1)") (class "Default")
      (node (ref "R402") (pin "2") (pinfunction "2_2") (pintype "passive"))
      (node (ref "U401") (pin "12") (pinfunction "I/O1_12") (pintype "bidirectional"))
    )
    (net (code "70") (name "Net-(U401-I{slash}O2)") (class "Default")
      (node (ref "R403") (pin "2") (pinfunction "2_2") (pintype "passive"))
      (node (ref "U401") (pin "13") (pinfunction "I/O2_13") (pintype "bidirectional"))
    )
    (net (code "71") (name "Net-(U401-I{slash}O3)") (class "Default")
      (node (ref "R404") (pin "1") (pinfunction "1_1") (pintype "passive"))
      (node (ref "U401") (pin "15") (pinfunction "I/O3_15") (pintype "bidirectional"))
    )
    (net (code "72") (name "Net-(U401-I{slash}O4)") (class "Default")
      (node (ref "R405") (pin "1") (pinfunction "1_1") (pintype "passive"))
      (node (ref "U401") (pin "16") (pinfunction "I/O4_16") (pintype "bidirectional"))
    )
    (net (code "73") (name "Net-(U401-I{slash}O5)") (class "Default")
      (node (ref "R406") (pin "1") (pinfunction "1_1") (pintype "passive"))
      (node (ref "U401") (pin "17") (pinfunction "I/O5_17") (pintype "bidirectional"))
    )
    (net (code "74") (name "Net-(U401-I{slash}O6)") (class "Default")
      (node (ref "R407") (pin "1") (pinfunction "1_1") (pintype "passive"))
      (node (ref "U401") (pin "18") (pinfunction "I/O6_18") (pintype "bidirectional"))
    )
    (net (code "75") (name "Net-(U601-CON)") (class "Default")
      (node (ref "C602") (pin "1") (pinfunction "1_1") (pintype "passive"))
      (node (ref "U601") (pin "5") (pinfunction "CON_5") (pintype "input"))
    )
    (net (code "76") (name "Net-(U601-DIS)") (class "Default")
      (node (ref "R601") (pin "1") (pinfunction "1_1") (pintype "passive"))
      (node (ref "R602") (pin "2") (pinfunction "2_2") (pintype "passive"))
      (node (ref "U601") (pin "7") (pinfunction "DIS_7") (pintype "input"))
    )
    (net (code "77") (name "Net-(U701-1D)") (class "Default")
      (node (ref "U701") (pin "2") (pinfunction "1D_2") (pintype "bidirectional"))
      (node (ref "U701") (pin "6") (pinfunction "1~{Q}_6") (pintype "bidirectional"))
    )
    (net (code "78") (name "Net-(U701-2D)") (class "Default")
      (node (ref "U701") (pin "12") (pinfunction "2D_12") (pintype "bidirectional"))
      (node (ref "U701") (pin "8") (pinfunction "2~{Q}_8") (pintype "bidirectional"))
    )
    (net (code "79") (name "S0") (class "Default")
      (node (ref "U1001") (pin "4") (pinfunction "G1_4") (pintype "bidirectional"))
      (node (ref "U201") (pin "15") (pinfunction "CH_X2_15") (pintype "bidirectional"))
      (node (ref "XOR_301") (pin "6") (pinfunction "Y2_6") (pintype "bidirectional"))
    )
    (net (code "80") (name "S1") (class "Default")
      (node (ref "U1001") (pin "2") (pinfunction "G2_2") (pintype "bidirectional"))
      (node (ref "U201") (pin "2") (pinfunction "CH_Y2_2") (pintype "bidirectional"))
      (node (ref "XOR_301") (pin "8") (pinfunction "Y3_8") (pintype "bidirectional"))
    )
    (net (code "81") (name "S2") (class "Default")
      (node (ref "U1002") (pin "4") (pinfunction "G1_4") (pintype "bidirectional"))
      (node (ref "U202") (pin "15") (pinfunction "CH_X2_15") (pintype "bidirectional"))
      (node (ref "XOR_302") (pin "6") (pinfunction "Y2_6") (pintype "bidirectional"))
    )
    (net (code "82") (name "S3") (class "Default")
      (node (ref "U1002") (pin "2") (pinfunction "G2_2") (pintype "bidirectional"))
      (node (ref "U202") (pin "2") (pinfunction "CH_Y2_2") (pintype "bidirectional"))
      (node (ref "XOR_302") (pin "8") (pinfunction "Y3_8") (pintype "bidirectional"))
    )
    (net (code "83") (name "VCC") (class "Default")
      (node (ref "AND_301") (pin "14") (pinfunction "VCC_14") (pintype "bidirectional"))
      (node (ref "AND_302") (pin "14") (pinfunction "VCC_14") (pintype "bidirectional"))
      (node (ref "C201") (pin "1") (pinfunction "1_1") (pintype "passive"))
      (node (ref "C202") (pin "1") (pinfunction "1_1") (pintype "passive"))
      (node (ref "C203") (pin "1") (pinfunction "1_1") (pintype "passive"))
      (node (ref "C301") (pin "1") (pinfunction "1_1") (pintype "passive"))
      (node (ref "C302") (pin "1") (pinfunction "1_1") (pintype "passive"))
      (node (ref "C303") (pin "1") (pinfunction "1_1") (pintype "passive"))
      (node (ref "C304") (pin "1") (pinfunction "1_1") (pintype "passive"))
      (node (ref "C305") (pin "1") (pinfunction "1_1") (pintype "passive"))
      (node (ref "C401") (pin "1") (pinfunction "1_1") (pintype "passive"))
      (node (ref "C501") (pin "1") (pinfunction "1_1") (pintype "passive"))
      (node (ref "C603") (pin "1") (pinfunction "1_1") (pintype "passive"))
      (node (ref "C701") (pin "1") (pinfunction "1_1") (pintype "passive"))
      (node (ref "OR_301") (pin "14") (pinfunction "VCC_14") (pintype "bidirectional"))
      (node (ref "R1001") (pin "2") (pinfunction "2_2") (pintype "passive"))
      (node (ref "R1002") (pin "2") (pinfunction "2_2") (pintype "passive"))
      (node (ref "R1003") (pin "2") (pinfunction "2_2") (pintype "passive"))
      (node (ref "R1004") (pin "2") (pinfunction "2_2") (pintype "passive"))
      (node (ref "R1005") (pin "2") (pinfunction "2_2") (pintype "passive"))
      (node (ref "R601") (pin "2") (pinfunction "2_2") (pintype "passive"))
      (node (ref "S901") (pin "VCC") (pinfunction "P$B_VCC") (pintype "bidirectional"))
      (node (ref "S902") (pin "VCC") (pinfunction "P$B_VCC") (pintype "bidirectional"))
      (node (ref "S903") (pin "VCC") (pinfunction "P$B_VCC") (pintype "bidirectional"))
      (node (ref "S904") (pin "VCC") (pinfunction "P$B_VCC") (pintype "bidirectional"))
      (node (ref "S905") (pin "VCC") (pinfunction "P$B_VCC") (pintype "bidirectional"))
      (node (ref "S906") (pin "VCC") (pinfunction "P$B_VCC") (pintype "bidirectional"))
      (node (ref "S907") (pin "VCC") (pinfunction "P$B_VCC") (pintype "bidirectional"))
      (node (ref "S908") (pin "VCC") (pinfunction "P$B_VCC") (pintype "bidirectional"))
      (node (ref "T102") (pin "5") (pinfunction "D_5") (pintype "passive"))
      (node (ref "T102") (pin "6") (pinfunction "D_6") (pintype "passive"))
      (node (ref "T102") (pin "7") (pinfunction "D_7") (pintype "passive"))
      (node (ref "T102") (pin "8") (pinfunction "D_8") (pintype "passive"))
      (node (ref "T102") (pin "9") (pinfunction "D_9") (pintype "passive"))
      (node (ref "U201") (pin "16") (pinfunction "VDD_16") (pintype "bidirectional"))
      (node (ref "U202") (pin "16") (pinfunction "VDD_16") (pintype "bidirectional"))
      (node (ref "U203") (pin "16") (pinfunction "VDD_16") (pintype "bidirectional"))
      (node (ref "U401") (pin "27") (pinfunction "~{WE}_27") (pintype "bidirectional"))
      (node (ref "U401") (pin "28") (pinfunction "VCC_28") (pintype "bidirectional"))
      (node (ref "U501") (pin "16") (pinfunction "VCC_16") (pintype "bidirectional"))
      (node (ref "U601") (pin "4") (pinfunction "/RES_4") (pintype "input"))
      (node (ref "U601") (pin "8") (pinfunction "VCC+_8") (pintype "power_in"))
      (node (ref "U701") (pin "1") (pinfunction "1~{CLR}_1") (pintype "bidirectional"))
      (node (ref "U701") (pin "10") (pinfunction "2~{PRE}_10") (pintype "bidirectional"))
      (node (ref "U701") (pin "13") (pinfunction "2~{CLR}_13") (pintype "bidirectional"))
      (node (ref "U701") (pin "14") (pinfunction "VCC_14") (pintype "bidirectional"))
      (node (ref "U701") (pin "4") (pinfunction "1~{PRE}_4") (pintype "bidirectional"))
      (node (ref "XOR_301") (pin "14") (pinfunction "VCC_14") (pintype "bidirectional"))
      (node (ref "XOR_302") (pin "14") (pinfunction "VCC_14") (pintype "bidirectional"))
    )
    (net (code "84") (name "unconnected-(U401-I{slash}O7-Pad19)") (class "Default")
      (node (ref "U401") (pin "19") (pinfunction "I/O7_19") (pintype "bidirectional"))
    )
    (net (code "85") (name "unconnected-(U401-N.C.-Pad26)") (class "Default")
      (node (ref "U401") (pin "26") (pinfunction "N.C._26") (pintype "bidirectional"))
    )
    (net (code "86") (name "unconnected-(U401-RDY-Pad1)") (class "Default")
      (node (ref "U401") (pin "1") (pinfunction "RDY_1") (pintype "bidirectional"))
    )
    (net (code "87") (name "unconnected-(U501-Y6-Pad2)") (class "Default")
      (node (ref "U501") (pin "2") (pinfunction "Y6_2") (pintype "bidirectional"))
    )
    (net (code "88") (name "unconnected-(U501-Y7-Pad4)") (class "Default")
      (node (ref "U501") (pin "4") (pinfunction "Y7_4") (pintype "bidirectional"))
    )
    (net (code "89") (name "unconnected-(U1003-D2-Pad7)") (class "Default")
      (node (ref "U1003") (pin "7") (pinfunction "D2_7") (pintype "bidirectional"))
    )
    (net (code "90") (name "unconnected-(U1003-D2_1-Pad8)") (class "Default")
      (node (ref "U1003") (pin "8") (pinfunction "D2_1_8") (pintype "bidirectional"))
    )
    (net (code "91") (name "unconnected-(U1003-G2-Pad2)") (class "Default")
      (node (ref "U1003") (pin "2") (pinfunction "G2_2") (pintype "bidirectional"))
    )
    (net (code "92") (name "unconnected-(U1003-S2-Pad1)") (class "Default")
      (node (ref "U1003") (pin "1") (pinfunction "S2_1") (pintype "bidirectional"))
    )
  )
)
